# v2_4_button.net
KiCad netlist of a schematic drawn in EAGLE
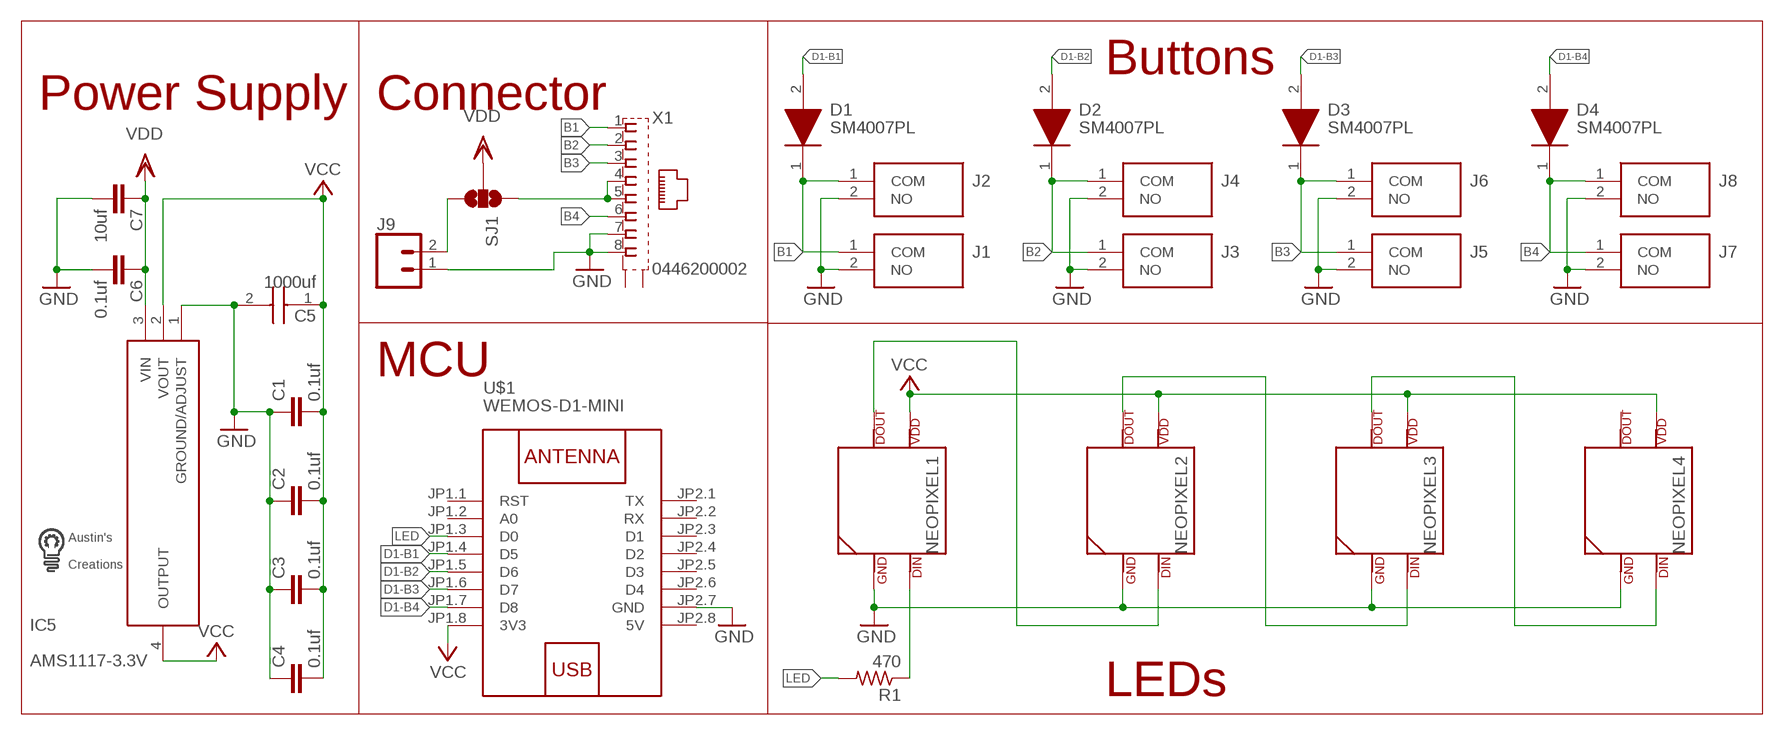
[diagram p0: schematic, sheet 1]

(export (version "E")
  (design (tool "Eeschema 10.0.6"))
  (components
    (comp (ref "C1")
      (value "0.1uf")
      (footprint "eagle-import:C0603")
      (libsource (lib "eagle-import") (part "C-EUC0603"))
    )
    (comp (ref "C2")
      (value "0.1uf")
      (footprint "eagle-import:C0603")
      (libsource (lib "eagle-import") (part "C-EUC0603"))
    )
    (comp (ref "C3")
      (value "0.1uf")
      (footprint "eagle-import:C0603")
      (libsource (lib "eagle-import") (part "C-EUC0603"))
    )
    (comp (ref "C4")
      (value "0.1uf")
      (footprint "eagle-import:C0603")
      (libsource (lib "eagle-import") (part "C-EUC0603"))
    )
    (comp (ref "C5")
      (value "1000uf")
      (footprint "eagle-import:CAPAE1030X1050N")
      (fields
        (field (name "MANUFACTURER_PART_NUMBER") "EEE-0JA102P")
        (field (name "MOUSER_PART_NUMBER") "667-EEE-0JA102P")
      )
      (libsource (lib "eagle-import") (part "EEE-0JA102P"))
    )
    (comp (ref "C6")
      (value "0.1uf")
      (footprint "eagle-import:C0603")
      (libsource (lib "eagle-import") (part "C-EUC0603"))
    )
    (comp (ref "C7")
      (value "10uf")
      (footprint "eagle-import:C0603")
      (libsource (lib "eagle-import") (part "C-EUC0603"))
    )
    (comp (ref "D1")
      (value "SM4007PL")
      (footprint "eagle-import:SODFL3718X125N")
      (libsource (lib "eagle-import") (part "SM4007PL"))
    )
    (comp (ref "D2")
      (value "SM4007PL")
      (footprint "eagle-import:SODFL3718X125N")
      (libsource (lib "eagle-import") (part "SM4007PL"))
    )
    (comp (ref "D3")
      (value "SM4007PL")
      (footprint "eagle-import:SODFL3718X125N")
      (libsource (lib "eagle-import") (part "SM4007PL"))
    )
    (comp (ref "D4")
      (value "SM4007PL")
      (footprint "eagle-import:SODFL3718X125N")
      (libsource (lib "eagle-import") (part "SM4007PL"))
    )
    (comp (ref "IC5")
      (value "AMS1117-3.3V")
      (footprint "eagle-import:SOT229P700X180-4N")
      (fields (field (name "MANUFACTURER_PART_NUMBER") "ams1117-3.3v"))
      (libsource (lib "eagle-import") (part "AMS1117-3.3V"))
    )
    (comp (ref "J1")
      (value "PTS636_SM25F_SMTR_LFS")
      (footprint "eagle-import:PTS636SM25FSMTRLFS")
      (fields
        (field (name "ARROW_PART_NUMBER") "PTS636 SM25F SMTR LFS")
        (field (name "MOUSER_PART_NUMBER") "611-PTS636SM25FSMTRL")
      )
      (libsource (lib "eagle-import") (part "PTS636_SM25F_SMTR_LFS"))
    )
    (comp (ref "J2")
      (value "PTS636_SM25F_SMTR_LFS")
      (footprint "eagle-import:PTS636SM25FSMTRLFS")
      (fields
        (field (name "ARROW_PART_NUMBER") "PTS636 SM25F SMTR LFS")
        (field (name "MOUSER_PART_NUMBER") "611-PTS636SM25FSMTRL")
      )
      (libsource (lib "eagle-import") (part "PTS636_SM25F_SMTR_LFS"))
    )
    (comp (ref "J3")
      (value "PTS636_SM25F_SMTR_LFS")
      (footprint "eagle-import:PTS636SM25FSMTRLFS")
      (fields
        (field (name "ARROW_PART_NUMBER") "PTS636 SM25F SMTR LFS")
        (field (name "MOUSER_PART_NUMBER") "611-PTS636SM25FSMTRL")
      )
      (libsource (lib "eagle-import") (part "PTS636_SM25F_SMTR_LFS"))
    )
    (comp (ref "J4")
      (value "PTS636_SM25F_SMTR_LFS")
      (footprint "eagle-import:PTS636SM25FSMTRLFS")
      (fields
        (field (name "ARROW_PART_NUMBER") "PTS636 SM25F SMTR LFS")
        (field (name "MOUSER_PART_NUMBER") "611-PTS636SM25FSMTRL")
      )
      (libsource (lib "eagle-import") (part "PTS636_SM25F_SMTR_LFS"))
    )
    (comp (ref "J5")
      (value "PTS636_SM25F_SMTR_LFS")
      (footprint "eagle-import:PTS636SM25FSMTRLFS")
      (fields
        (field (name "ARROW_PART_NUMBER") "PTS636 SM25F SMTR LFS")
        (field (name "MOUSER_PART_NUMBER") "611-PTS636SM25FSMTRL")
      )
      (libsource (lib "eagle-import") (part "PTS636_SM25F_SMTR_LFS"))
    )
    (comp (ref "J6")
      (value "PTS636_SM25F_SMTR_LFS")
      (footprint "eagle-import:PTS636SM25FSMTRLFS")
      (fields
        (field (name "ARROW_PART_NUMBER") "PTS636 SM25F SMTR LFS")
        (field (name "MOUSER_PART_NUMBER") "611-PTS636SM25FSMTRL")
      )
      (libsource (lib "eagle-import") (part "PTS636_SM25F_SMTR_LFS"))
    )
    (comp (ref "J7")
      (value "PTS636_SM25F_SMTR_LFS")
      (footprint "eagle-import:PTS636SM25FSMTRLFS")
      (fields
        (field (name "ARROW_PART_NUMBER") "PTS636 SM25F SMTR LFS")
        (field (name "MOUSER_PART_NUMBER") "611-PTS636SM25FSMTRL")
      )
      (libsource (lib "eagle-import") (part "PTS636_SM25F_SMTR_LFS"))
    )
    (comp (ref "J8")
      (value "PTS636_SM25F_SMTR_LFS")
      (footprint "eagle-import:PTS636SM25FSMTRLFS")
      (fields
        (field (name "ARROW_PART_NUMBER") "PTS636 SM25F SMTR LFS")
        (field (name "MOUSER_PART_NUMBER") "611-PTS636SM25FSMTRL")
      )
      (libsource (lib "eagle-import") (part "PTS636_SM25F_SMTR_LFS"))
    )
    (comp (ref "J9")
      (value "CONN_025MM")
      (footprint "eagle-import:SCREWTERMINAL-5MM-2")
      (libsource (lib "eagle-import") (part "CONN_025MM"))
    )
    (comp (ref "NEOPIXEL1")
      (value "SK6812NEOPIXEL5050")
      (footprint "eagle-import:SK6812")
      (libsource (lib "eagle-import") (part "SK68125050NEOPIXEL"))
    )
    (comp (ref "NEOPIXEL2")
      (value "SK6812NEOPIXEL5050")
      (footprint "eagle-import:SK6812")
      (libsource (lib "eagle-import") (part "SK68125050NEOPIXEL"))
    )
    (comp (ref "NEOPIXEL3")
      (value "SK6812NEOPIXEL5050")
      (footprint "eagle-import:SK6812")
      (libsource (lib "eagle-import") (part "SK68125050NEOPIXEL"))
    )
    (comp (ref "NEOPIXEL4")
      (value "SK6812NEOPIXEL5050")
      (footprint "eagle-import:SK6812")
      (libsource (lib "eagle-import") (part "SK68125050NEOPIXEL"))
    )
    (comp (ref "R1")
      (value "470")
      (footprint "eagle-import:R0603")
      (libsource (lib "eagle-import") (part "R-US_R0603"))
    )
    (comp (ref "SJ1")
      (value "SOLDERJUMPER_2WAYPASTE1&2")
      (footprint "eagle-import:SJ_3_PASTE1&2")
      (libsource (lib "eagle-import") (part "SOLDERJUMPER_2WAYPASTE1&2"))
    )
    (comp (ref "U$1")
      (value "WEMOS-D1-MINI")
      (footprint "eagle-import:WEMOS-D1-MINI")
      (libsource (lib "eagle-import") (part "WEMOS-D1-MINI"))
    )
    (comp (ref "U$2")
      (value "LOGO")
      (footprint "eagle-import:LOGO")
      (libsource (lib "eagle-import") (part "LOGO"))
    )
    (comp (ref "X1")
      (value "0446200002")
      (footprint "eagle-import:0446200002")
      (fields (field (name "MF") "MOLEX"))
      (libsource (lib "eagle-import") (part "0446200002"))
    )
  )
  (nets
    (net (code "1") (name "/5V") (class "Default")
      (node (ref "U$1") (pin "JP2.8") (pinfunction "5V_JP2.8") (pintype "power_in"))
    )
    (net (code "2") (name "B1") (class "Default")
      (node (ref "D1") (pin "1") (pinfunction "K_1") (pintype "bidirectional"))
      (node (ref "J1") (pin "1") (pinfunction "COM_1") (pintype "bidirectional"))
      (node (ref "J2") (pin "1") (pinfunction "COM_1") (pintype "bidirectional"))
      (node (ref "X1") (pin "1") (pinfunction "1_1") (pintype "passive"))
    )
    (net (code "3") (name "B2") (class "Default")
      (node (ref "D2") (pin "1") (pinfunction "K_1") (pintype "bidirectional"))
      (node (ref "J3") (pin "1") (pinfunction "COM_1") (pintype "bidirectional"))
      (node (ref "J4") (pin "1") (pinfunction "COM_1") (pintype "bidirectional"))
      (node (ref "X1") (pin "2") (pinfunction "2_2") (pintype "passive"))
    )
    (net (code "4") (name "B3") (class "Default")
      (node (ref "D3") (pin "1") (pinfunction "K_1") (pintype "bidirectional"))
      (node (ref "J5") (pin "1") (pinfunction "COM_1") (pintype "bidirectional"))
      (node (ref "J6") (pin "1") (pinfunction "COM_1") (pintype "bidirectional"))
      (node (ref "X1") (pin "3") (pinfunction "3_3") (pintype "passive"))
    )
    (net (code "5") (name "B4") (class "Default")
      (node (ref "D4") (pin "1") (pinfunction "K_1") (pintype "bidirectional"))
      (node (ref "J7") (pin "1") (pinfunction "COM_1") (pintype "bidirectional"))
      (node (ref "J8") (pin "1") (pinfunction "COM_1") (pintype "bidirectional"))
      (node (ref "X1") (pin "6") (pinfunction "6_6") (pintype "passive"))
    )
    (net (code "6") (name "D1-B1") (class "Default")
      (node (ref "D1") (pin "2") (pinfunction "A_2") (pintype "bidirectional"))
      (node (ref "U$1") (pin "JP1.4") (pinfunction "D5_JP1.4") (pintype "bidirectional"))
    )
    (net (code "7") (name "D1-B2") (class "Default")
      (node (ref "D2") (pin "2") (pinfunction "A_2") (pintype "bidirectional"))
      (node (ref "U$1") (pin "JP1.5") (pinfunction "D6_JP1.5") (pintype "bidirectional"))
    )
    (net (code "8") (name "D1-B3") (class "Default")
      (node (ref "D3") (pin "2") (pinfunction "A_2") (pintype "bidirectional"))
      (node (ref "U$1") (pin "JP1.6") (pinfunction "D7_JP1.6") (pintype "bidirectional"))
    )
    (net (code "9") (name "D1-B4") (class "Default")
      (node (ref "D4") (pin "2") (pinfunction "A_2") (pintype "bidirectional"))
      (node (ref "U$1") (pin "JP1.7") (pinfunction "D8_JP1.7") (pintype "bidirectional"))
    )
    (net (code "10") (name "GND") (class "Default")
      (node (ref "C1") (pin "1") (pinfunction "1_1") (pintype "passive"))
      (node (ref "C2") (pin "1") (pinfunction "1_1") (pintype "passive"))
      (node (ref "C3") (pin "1") (pinfunction "1_1") (pintype "passive"))
      (node (ref "C4") (pin "1") (pinfunction "1_1") (pintype "passive"))
      (node (ref "C5") (pin "2") (pinfunction "-_2") (pintype "bidirectional"))
      (node (ref "C6") (pin "2") (pinfunction "2_2") (pintype "passive"))
      (node (ref "C7") (pin "2") (pinfunction "2_2") (pintype "passive"))
      (node (ref "IC5") (pin "1") (pinfunction "GROUND/ADJUST_1") (pintype "bidirectional"))
      (node (ref "J1") (pin "2") (pinfunction "NO_2") (pintype "bidirectional"))
      (node (ref "J2") (pin "2") (pinfunction "NO_2") (pintype "bidirectional"))
      (node (ref "J3") (pin "2") (pinfunction "NO_2") (pintype "bidirectional"))
      (node (ref "J4") (pin "2") (pinfunction "NO_2") (pintype "bidirectional"))
      (node (ref "J5") (pin "2") (pinfunction "NO_2") (pintype "bidirectional"))
      (node (ref "J6") (pin "2") (pinfunction "NO_2") (pintype "bidirectional"))
      (node (ref "J7") (pin "2") (pinfunction "NO_2") (pintype "bidirectional"))
      (node (ref "J8") (pin "2") (pinfunction "NO_2") (pintype "bidirectional"))
      (node (ref "J9") (pin "1") (pinfunction "1_1") (pintype "passive"))
      (node (ref "NEOPIXEL1") (pin "3") (pinfunction "GND_3") (pintype "bidirectional"))
      (node (ref "NEOPIXEL2") (pin "3") (pinfunction "GND_3") (pintype "bidirectional"))
      (node (ref "NEOPIXEL3") (pin "3") (pinfunction "GND_3") (pintype "bidirectional"))
      (node (ref "NEOPIXEL4") (pin "3") (pinfunction "GND_3") (pintype "bidirectional"))
      (node (ref "U$1") (pin "JP2.7") (pinfunction "GND_JP2.7") (pintype "power_in"))
      (node (ref "X1") (pin "7") (pinfunction "7_7") (pintype "passive"))
      (node (ref "X1") (pin "8") (pinfunction "8_8") (pintype "passive"))
    )
    (net (code "11") (name "LED") (class "Default")
      (node (ref "R1") (pin "2") (pinfunction "2_2") (pintype "passive"))
      (node (ref "U$1") (pin "JP1.3") (pinfunction "D0_JP1.3") (pintype "bidirectional"))
    )
    (net (code "12") (name "Net-(J9-Pad2)") (class "Default")
      (node (ref "J9") (pin "2") (pinfunction "2_2") (pintype "passive"))
      (node (ref "SJ1") (pin "3") (pinfunction "3_3") (pintype "passive"))
    )
    (net (code "13") (name "Net-(NEOPIXEL1-DIN)") (class "Default")
      (node (ref "NEOPIXEL1") (pin "4") (pinfunction "DIN_4") (pintype "bidirectional"))
      (node (ref "R1") (pin "1") (pinfunction "1_1") (pintype "passive"))
    )
    (net (code "14") (name "Net-(NEOPIXEL1-DOUT)") (class "Default")
      (node (ref "NEOPIXEL1") (pin "2") (pinfunction "DOUT_2") (pintype "bidirectional"))
      (node (ref "NEOPIXEL2") (pin "4") (pinfunction "DIN_4") (pintype "bidirectional"))
    )
    (net (code "15") (name "Net-(NEOPIXEL2-DOUT)") (class "Default")
      (node (ref "NEOPIXEL2") (pin "2") (pinfunction "DOUT_2") (pintype "bidirectional"))
      (node (ref "NEOPIXEL3") (pin "4") (pinfunction "DIN_4") (pintype "bidirectional"))
    )
    (net (code "16") (name "Net-(NEOPIXEL3-DOUT)") (class "Default")
      (node (ref "NEOPIXEL3") (pin "2") (pinfunction "DOUT_2") (pintype "bidirectional"))
      (node (ref "NEOPIXEL4") (pin "4") (pinfunction "DIN_4") (pintype "bidirectional"))
    )
    (net (code "17") (name "Net-(SJ1-Pad1)") (class "Default")
      (node (ref "SJ1") (pin "1") (pinfunction "1_1") (pintype "passive"))
      (node (ref "X1") (pin "4") (pinfunction "4_4") (pintype "passive"))
      (node (ref "X1") (pin "5") (pinfunction "5_5") (pintype "passive"))
    )
    (net (code "18") (name "VCC") (class "Default")
      (node (ref "C1") (pin "2") (pinfunction "2_2") (pintype "passive"))
      (node (ref "C2") (pin "2") (pinfunction "2_2") (pintype "passive"))
      (node (ref "C3") (pin "2") (pinfunction "2_2") (pintype "passive"))
      (node (ref "C4") (pin "2") (pinfunction "2_2") (pintype "passive"))
      (node (ref "C5") (pin "1") (pinfunction "+_1") (pintype "bidirectional"))
      (node (ref "IC5") (pin "2") (pinfunction "VOUT_2") (pintype "bidirectional"))
      (node (ref "IC5") (pin "4") (pinfunction "OUTPUT_4") (pintype "bidirectional"))
      (node (ref "NEOPIXEL1") (pin "1") (pinfunction "VDD_1") (pintype "bidirectional"))
      (node (ref "NEOPIXEL2") (pin "1") (pinfunction "VDD_1") (pintype "bidirectional"))
      (node (ref "NEOPIXEL3") (pin "1") (pinfunction "VDD_1") (pintype "bidirectional"))
      (node (ref "NEOPIXEL4") (pin "1") (pinfunction "VDD_1") (pintype "bidirectional"))
      (node (ref "U$1") (pin "JP1.8") (pinfunction "3V3_JP1.8") (pintype "power_in"))
    )
    (net (code "19") (name "VDD") (class "Default")
      (node (ref "C6") (pin "1") (pinfunction "1_1") (pintype "passive"))
      (node (ref "C7") (pin "1") (pinfunction "1_1") (pintype "passive"))
      (node (ref "IC5") (pin "3") (pinfunction "VIN_3") (pintype "bidirectional"))
      (node (ref "SJ1") (pin "2") (pinfunction "2_2") (pintype "passive"))
    )
    (net (code "20") (name "unconnected-(NEOPIXEL4-DOUT-Pad2)") (class "Default")
      (node (ref "NEOPIXEL4") (pin "2") (pinfunction "DOUT_2") (pintype "bidirectional"))
    )
    (net (code "21") (name "unconnected-(U$1-A0-PadJP1.2)") (class "Default")
      (node (ref "U$1") (pin "JP1.2") (pinfunction "A0_JP1.2") (pintype "bidirectional"))
    )
    (net (code "22") (name "unconnected-(U$1-D1-PadJP2.3)") (class "Default")
      (node (ref "U$1") (pin "JP2.3") (pinfunction "D1_JP2.3") (pintype "bidirectional"))
    )
    (net (code "23") (name "unconnected-(U$1-D2-PadJP2.4)") (class "Default")
      (node (ref "U$1") (pin "JP2.4") (pinfunction "D2_JP2.4") (pintype "bidirectional"))
    )
    (net (code "24") (name "unconnected-(U$1-D3-PadJP2.5)") (class "Default")
      (node (ref "U$1") (pin "JP2.5") (pinfunction "D3_JP2.5") (pintype "bidirectional"))
    )
    (net (code "25") (name "unconnected-(U$1-D4-PadJP2.6)") (class "Default")
      (node (ref "U$1") (pin "JP2.6") (pinfunction "D4_JP2.6") (pintype "bidirectional"))
    )
    (net (code "26") (name "unconnected-(U$1-RST-PadJP1.1)") (class "Default")
      (node (ref "U$1") (pin "JP1.1") (pinfunction "RST_JP1.1") (pintype "bidirectional"))
    )
    (net (code "27") (name "unconnected-(U$1-RX-PadJP2.2)") (class "Default")
      (node (ref "U$1") (pin "JP2.2") (pinfunction "RX_JP2.2") (pintype "bidirectional"))
    )
    (net (code "28") (name "unconnected-(U$1-TX-PadJP2.1)") (class "Default")
      (node (ref "U$1") (pin "JP2.1") (pinfunction "TX_JP2.1") (pintype "bidirectional"))
    )
    (net (code "29") (name "unconnected-(X1-S1-PadS@1)") (class "Default")
      (node (ref "X1") (pin "S@1") (pinfunction "S1_S@1") (pintype "passive"))
    )
    (net (code "30") (name "unconnected-(X1-S2-PadS@2)") (class "Default")
      (node (ref "X1") (pin "S@2") (pinfunction "S2_S@2") (pintype "passive"))
    )
  )
)
